# new_uvbox.net
KiCad netlist of a schematic drawn in EAGLE
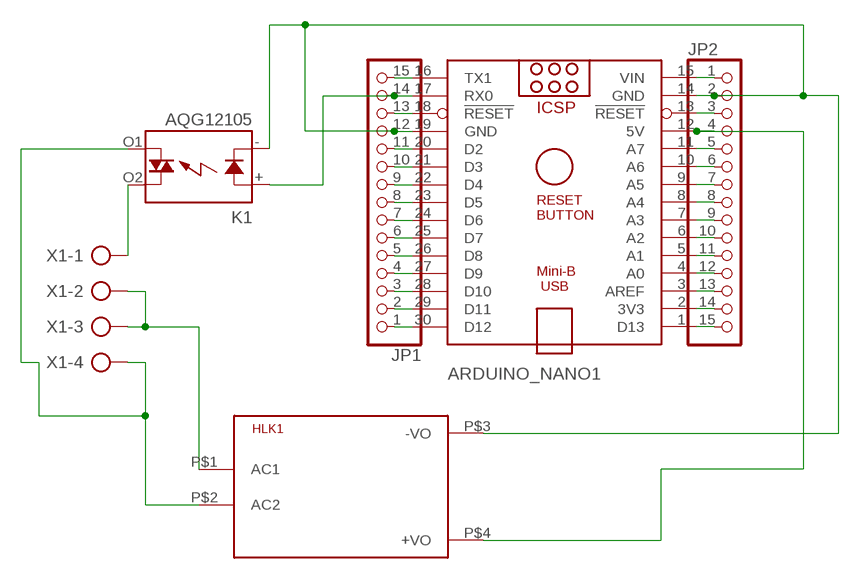
[diagram p0: schematic, sheet 1]

(export (version "E")
  (design (tool "Eeschema 10.0.6"))
  (components
    (comp (ref "ARDUINO_NANO1")
      (value "ARDUINO_NANO")
      (footprint "eagle-import:ARDUINO_NANO")
      (libsource (lib "eagle-import") (part "ARDUINO_NANO"))
    )
    (comp (ref "HLK1")
      (value "HLK-PM013W")
      (footprint "eagle-import:HLK-PM01")
      (libsource (lib "eagle-import") (part "HLK-PM013W"))
    )
    (comp (ref "JP1")
      (value "PINHD-1X15")
      (footprint "eagle-import:1X15")
      (libsource (lib "eagle-import") (part "PINHD-1X15"))
    )
    (comp (ref "JP2")
      (value "PINHD-1X15")
      (footprint "eagle-import:1X15")
      (libsource (lib "eagle-import") (part "PINHD-1X15"))
    )
    (comp (ref "K1")
      (value "AQG12105")
      (footprint "eagle-import:AQG")
      (fields (field (name "MF") "AROMAT/ MATSUSHITA"))
      (libsource (lib "eagle-import") (part "AQG12105"))
    )
    (comp (ref "X1")
      (value "AK300/4")
      (footprint "eagle-import:AK300_4")
      (libsource (lib "eagle-import") (part "AK300/4"))
    )
  )
  (nets
    (net (code "1") (name "Net-(ARDUINO_NANO1-3V3)") (class "Default")
      (node (ref "ARDUINO_NANO1") (pin "2") (pinfunction "3V3_2") (pintype "output"))
      (node (ref "JP2") (pin "14") (pinfunction "14_14") (pintype "passive"))
    )
    (net (code "2") (name "Net-(ARDUINO_NANO1-5V)") (class "Default")
      (node (ref "ARDUINO_NANO1") (pin "12") (pinfunction "5V_12") (pintype "power_in"))
      (node (ref "HLK1") (pin "P$4") (pinfunction "+VO_P$4") (pintype "bidirectional"))
      (node (ref "JP2") (pin "4") (pinfunction "4_4") (pintype "passive"))
    )
    (net (code "3") (name "Net-(ARDUINO_NANO1-A0)") (class "Default")
      (node (ref "ARDUINO_NANO1") (pin "4") (pinfunction "A0_4") (pintype "bidirectional"))
      (node (ref "JP2") (pin "12") (pinfunction "12_12") (pintype "passive"))
    )
    (net (code "4") (name "Net-(ARDUINO_NANO1-A1)") (class "Default")
      (node (ref "ARDUINO_NANO1") (pin "5") (pinfunction "A1_5") (pintype "bidirectional"))
      (node (ref "JP2") (pin "11") (pinfunction "11_11") (pintype "passive"))
    )
    (net (code "5") (name "Net-(ARDUINO_NANO1-A2)") (class "Default")
      (node (ref "ARDUINO_NANO1") (pin "6") (pinfunction "A2_6") (pintype "bidirectional"))
      (node (ref "JP2") (pin "10") (pinfunction "10_10") (pintype "passive"))
    )
    (net (code "6") (name "Net-(ARDUINO_NANO1-A3)") (class "Default")
      (node (ref "ARDUINO_NANO1") (pin "7") (pinfunction "A3_7") (pintype "bidirectional"))
      (node (ref "JP2") (pin "9") (pinfunction "9_9") (pintype "passive"))
    )
    (net (code "7") (name "Net-(ARDUINO_NANO1-A4)") (class "Default")
      (node (ref "ARDUINO_NANO1") (pin "8") (pinfunction "A4_8") (pintype "bidirectional"))
      (node (ref "JP2") (pin "8") (pinfunction "8_8") (pintype "passive"))
    )
    (net (code "8") (name "Net-(ARDUINO_NANO1-A5)") (class "Default")
      (node (ref "ARDUINO_NANO1") (pin "9") (pinfunction "A5_9") (pintype "bidirectional"))
      (node (ref "JP2") (pin "7") (pinfunction "7_7") (pintype "passive"))
    )
    (net (code "9") (name "Net-(ARDUINO_NANO1-A6)") (class "Default")
      (node (ref "ARDUINO_NANO1") (pin "10") (pinfunction "A6_10") (pintype "bidirectional"))
      (node (ref "JP2") (pin "6") (pinfunction "6_6") (pintype "passive"))
    )
    (net (code "10") (name "Net-(ARDUINO_NANO1-A7)") (class "Default")
      (node (ref "ARDUINO_NANO1") (pin "11") (pinfunction "A7_11") (pintype "bidirectional"))
      (node (ref "JP2") (pin "5") (pinfunction "5_5") (pintype "passive"))
    )
    (net (code "11") (name "Net-(ARDUINO_NANO1-AREF)") (class "Default")
      (node (ref "ARDUINO_NANO1") (pin "3") (pinfunction "AREF_3") (pintype "input"))
      (node (ref "JP2") (pin "13") (pinfunction "13_13") (pintype "passive"))
    )
    (net (code "12") (name "Net-(ARDUINO_NANO1-D2)") (class "Default")
      (node (ref "ARDUINO_NANO1") (pin "20") (pinfunction "D2_20") (pintype "bidirectional"))
      (node (ref "JP1") (pin "11") (pinfunction "11_11") (pintype "passive"))
    )
    (net (code "13") (name "Net-(ARDUINO_NANO1-D3)") (class "Default")
      (node (ref "ARDUINO_NANO1") (pin "21") (pinfunction "D3_21") (pintype "bidirectional"))
      (node (ref "JP1") (pin "10") (pinfunction "10_10") (pintype "passive"))
    )
    (net (code "14") (name "Net-(ARDUINO_NANO1-D4)") (class "Default")
      (node (ref "ARDUINO_NANO1") (pin "22") (pinfunction "D4_22") (pintype "bidirectional"))
      (node (ref "JP1") (pin "9") (pinfunction "9_9") (pintype "passive"))
    )
    (net (code "15") (name "Net-(ARDUINO_NANO1-D5)") (class "Default")
      (node (ref "ARDUINO_NANO1") (pin "23") (pinfunction "D5_23") (pintype "bidirectional"))
      (node (ref "JP1") (pin "8") (pinfunction "8_8") (pintype "passive"))
    )
    (net (code "16") (name "Net-(ARDUINO_NANO1-D6)") (class "Default")
      (node (ref "ARDUINO_NANO1") (pin "24") (pinfunction "D6_24") (pintype "bidirectional"))
      (node (ref "JP1") (pin "7") (pinfunction "7_7") (pintype "passive"))
    )
    (net (code "17") (name "Net-(ARDUINO_NANO1-D7)") (class "Default")
      (node (ref "ARDUINO_NANO1") (pin "25") (pinfunction "D7_25") (pintype "bidirectional"))
      (node (ref "JP1") (pin "6") (pinfunction "6_6") (pintype "passive"))
    )
    (net (code "18") (name "Net-(ARDUINO_NANO1-D8)") (class "Default")
      (node (ref "ARDUINO_NANO1") (pin "26") (pinfunction "D8_26") (pintype "bidirectional"))
      (node (ref "JP1") (pin "5") (pinfunction "5_5") (pintype "passive"))
    )
    (net (code "19") (name "Net-(ARDUINO_NANO1-D9)") (class "Default")
      (node (ref "ARDUINO_NANO1") (pin "27") (pinfunction "D9_27") (pintype "bidirectional"))
      (node (ref "JP1") (pin "4") (pinfunction "4_4") (pintype "passive"))
    )
    (net (code "20") (name "Net-(ARDUINO_NANO1-D10)") (class "Default")
      (node (ref "ARDUINO_NANO1") (pin "28") (pinfunction "D10_28") (pintype "bidirectional"))
      (node (ref "JP1") (pin "3") (pinfunction "3_3") (pintype "passive"))
    )
    (net (code "21") (name "Net-(ARDUINO_NANO1-D11)") (class "Default")
      (node (ref "ARDUINO_NANO1") (pin "29") (pinfunction "D11_29") (pintype "bidirectional"))
      (node (ref "JP1") (pin "2") (pinfunction "2_2") (pintype "passive"))
    )
    (net (code "22") (name "Net-(ARDUINO_NANO1-D12)") (class "Default")
      (node (ref "ARDUINO_NANO1") (pin "30") (pinfunction "D12_30") (pintype "bidirectional"))
      (node (ref "JP1") (pin "1") (pinfunction "1_1") (pintype "passive"))
    )
    (net (code "23") (name "Net-(ARDUINO_NANO1-D13)") (class "Default")
      (node (ref "ARDUINO_NANO1") (pin "1") (pinfunction "D13_1") (pintype "bidirectional"))
      (node (ref "JP2") (pin "15") (pinfunction "15_15") (pintype "passive"))
    )
    (net (code "24") (name "Net-(ARDUINO_NANO1-RX0)") (class "Default")
      (node (ref "ARDUINO_NANO1") (pin "17") (pinfunction "RX0_17") (pintype "bidirectional"))
      (node (ref "JP1") (pin "14") (pinfunction "14_14") (pintype "passive"))
      (node (ref "K1") (pin "+") (pinfunction "A_+") (pintype "passive"))
    )
    (net (code "25") (name "Net-(ARDUINO_NANO1-TX1)") (class "Default")
      (node (ref "ARDUINO_NANO1") (pin "16") (pinfunction "TX1_16") (pintype "bidirectional"))
      (node (ref "JP1") (pin "15") (pinfunction "15_15") (pintype "passive"))
    )
    (net (code "26") (name "Net-(ARDUINO_NANO1-VIN)") (class "Default")
      (node (ref "ARDUINO_NANO1") (pin "15") (pinfunction "VIN_15") (pintype "power_in"))
      (node (ref "JP2") (pin "1") (pinfunction "1_1") (pintype "passive"))
    )
    (net (code "27") (name "Net-(ARDUINO_NANO1-~{RESET}-Pad13)") (class "Default")
      (node (ref "ARDUINO_NANO1") (pin "13") (pinfunction "~{RESET}_13") (pintype "input"))
      (node (ref "JP2") (pin "3") (pinfunction "3_3") (pintype "passive"))
    )
    (net (code "28") (name "Net-(ARDUINO_NANO1-~{RESET}-Pad18)") (class "Default")
      (node (ref "ARDUINO_NANO1") (pin "18") (pinfunction "~{RESET}_18") (pintype "input"))
      (node (ref "JP1") (pin "13") (pinfunction "13_13") (pintype "passive"))
    )
    (net (code "29") (name "Net-(HLK1--VO)") (class "Default")
      (node (ref "ARDUINO_NANO1") (pin "14") (pinfunction "GND_14") (pintype "power_in"))
      (node (ref "ARDUINO_NANO1") (pin "19") (pinfunction "GND_19") (pintype "power_in"))
      (node (ref "HLK1") (pin "P$3") (pinfunction "-VO_P$3") (pintype "bidirectional"))
      (node (ref "JP1") (pin "12") (pinfunction "12_12") (pintype "passive"))
      (node (ref "JP2") (pin "2") (pinfunction "2_2") (pintype "passive"))
      (node (ref "K1") (pin "-") (pinfunction "K_-") (pintype "passive"))
    )
    (net (code "30") (name "Net-(HLK1-AC1)") (class "Default")
      (node (ref "HLK1") (pin "P$1") (pinfunction "AC1_P$1") (pintype "bidirectional"))
      (node (ref "X1") (pin "2") (pinfunction "KL_2") (pintype "passive"))
      (node (ref "X1") (pin "3") (pinfunction "KL_3") (pintype "passive"))
    )
    (net (code "31") (name "Net-(HLK1-AC2)") (class "Default")
      (node (ref "HLK1") (pin "P$2") (pinfunction "AC2_P$2") (pintype "bidirectional"))
      (node (ref "K1") (pin "O1") (pinfunction "DS2_O1") (pintype "passive"))
      (node (ref "X1") (pin "4") (pinfunction "KL_4") (pintype "passive"))
    )
    (net (code "32") (name "Net-(K1-DS1)") (class "Default")
      (node (ref "K1") (pin "O2") (pinfunction "DS1_O2") (pintype "passive"))
      (node (ref "X1") (pin "1") (pinfunction "KL_1") (pintype "passive"))
    )
  )
)
